# LED_Chaser.net
KiCad netlist of a schematic drawn in Altium Designer
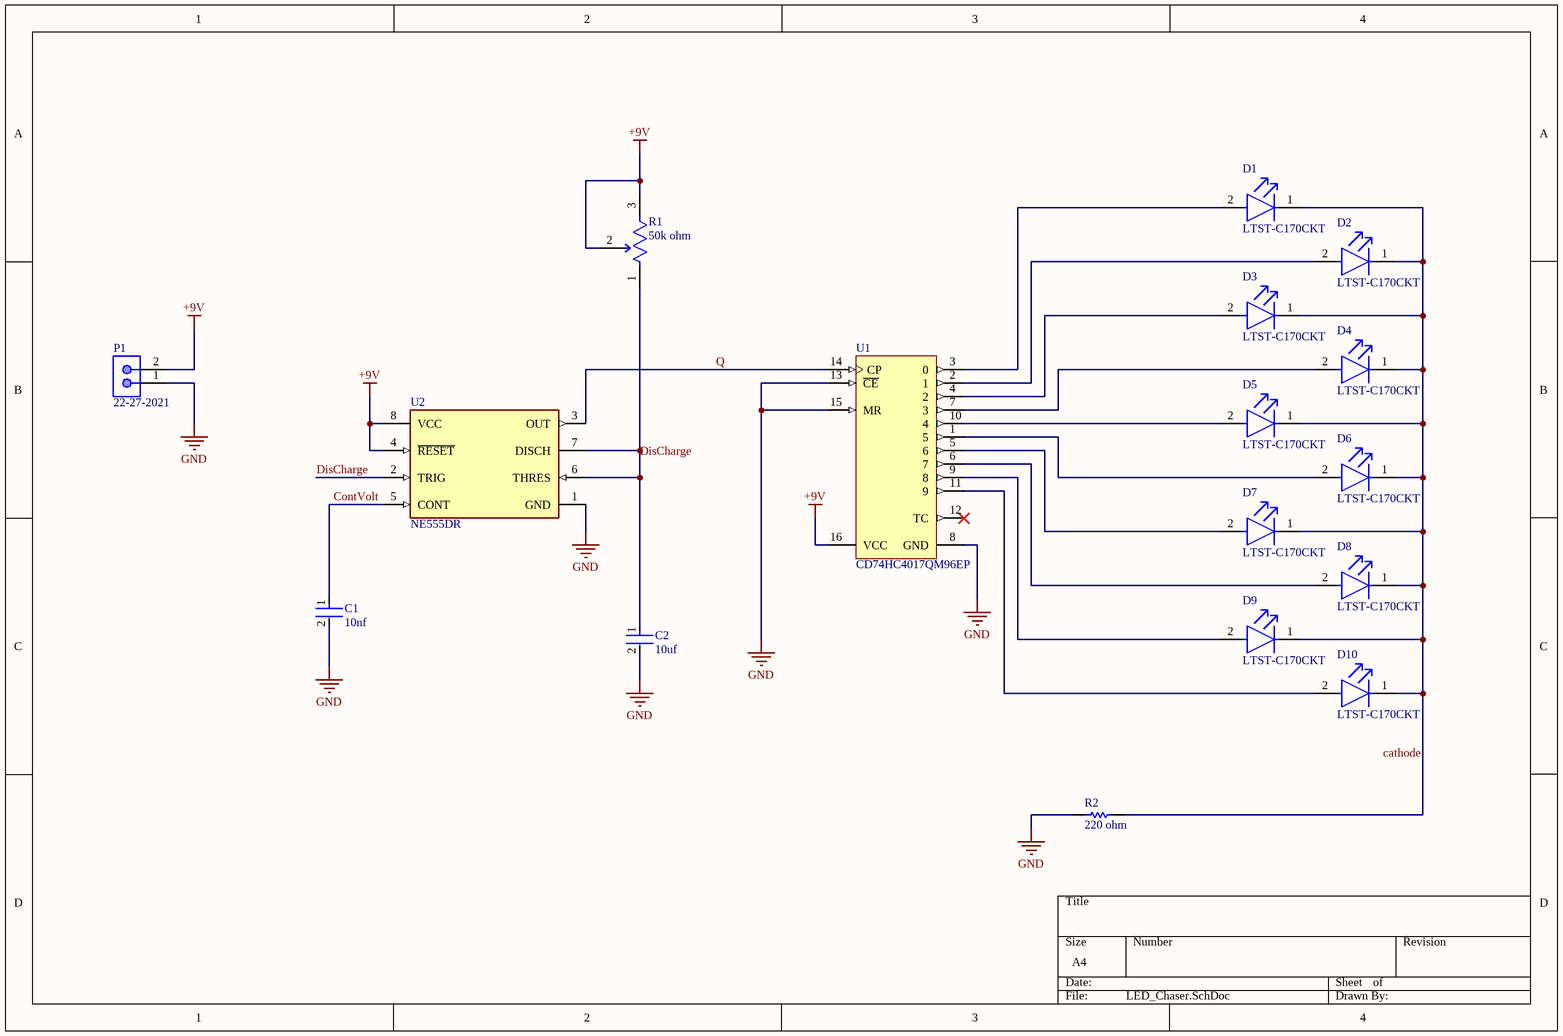
[diagram p0: LED_Chaser.SchDoc]

(export (version "E")
  (design (tool "Eeschema 10.0.6"))
  (components
    (comp (ref "C1")
      (value "10nf")
      (footprint "FP-CC0805-0_85-MFG")
      (description "CAP CER 0.1UF 50V X7R 0805")
      (fields (field (name "TOLERANCE") "0.1") (field (name "MANUFACTURER PART NUMBER") "CC0805KRX7R9BB104"))
      (libsource (lib "Altium Content Vault") (part "11868f565c42a9108669ba33697ecf6"))
    )
    (comp (ref "C2")
      (value "10uf")
      (footprint "FP-CC0805-0_85-MFG")
      (description "CAP CER 0.1UF 50V X7R 0805")
      (fields (field (name "TOLERANCE") "0.1") (field (name "MANUFACTURER PART NUMBER") "CC0805KRX7R9BB104"))
      (libsource (lib "Altium Content Vault") (part "11868f565c42a9108669ba33697ecf6"))
    )
    (comp (ref "D1")
      (value "LTST-C170CKT")
      (footprint "FP-LTST-C170CKT-MFG")
      (description "LED RED CLEAR SMD")
      (fields (field (name "VOLTAGE") "5V"))
      (libsource (lib "Altium Content Vault") (part "8706943c75ba83719d021d2fdc84c58"))
    )
    (comp (ref "D2")
      (value "LTST-C170CKT")
      (footprint "FP-LTST-C170CKT-MFG")
      (description "LED RED CLEAR SMD")
      (fields (field (name "VOLTAGE") "5V"))
      (libsource (lib "Altium Content Vault") (part "8706943c75ba83719d021d2fdc84c58"))
    )
    (comp (ref "D3")
      (value "LTST-C170CKT")
      (footprint "FP-LTST-C170CKT-MFG")
      (description "LED RED CLEAR SMD")
      (fields (field (name "VOLTAGE") "5V"))
      (libsource (lib "Altium Content Vault") (part "8706943c75ba83719d021d2fdc84c58"))
    )
    (comp (ref "D4")
      (value "LTST-C170CKT")
      (footprint "FP-LTST-C170CKT-MFG")
      (description "LED RED CLEAR SMD")
      (fields (field (name "VOLTAGE") "5V"))
      (libsource (lib "Altium Content Vault") (part "8706943c75ba83719d021d2fdc84c58"))
    )
    (comp (ref "D5")
      (value "LTST-C170CKT")
      (footprint "FP-LTST-C170CKT-MFG")
      (description "LED RED CLEAR SMD")
      (fields (field (name "VOLTAGE") "5V"))
      (libsource (lib "Altium Content Vault") (part "8706943c75ba83719d021d2fdc84c58"))
    )
    (comp (ref "D6")
      (value "LTST-C170CKT")
      (footprint "FP-LTST-C170CKT-MFG")
      (description "LED RED CLEAR SMD")
      (fields (field (name "VOLTAGE") "5V"))
      (libsource (lib "Altium Content Vault") (part "8706943c75ba83719d021d2fdc84c58"))
    )
    (comp (ref "D7")
      (value "LTST-C170CKT")
      (footprint "FP-LTST-C170CKT-MFG")
      (description "LED RED CLEAR SMD")
      (fields (field (name "VOLTAGE") "5V"))
      (libsource (lib "Altium Content Vault") (part "8706943c75ba83719d021d2fdc84c58"))
    )
    (comp (ref "D8")
      (value "LTST-C170CKT")
      (footprint "FP-LTST-C170CKT-MFG")
      (description "LED RED CLEAR SMD")
      (fields (field (name "VOLTAGE") "5V"))
      (libsource (lib "Altium Content Vault") (part "8706943c75ba83719d021d2fdc84c58"))
    )
    (comp (ref "D9")
      (value "LTST-C170CKT")
      (footprint "FP-LTST-C170CKT-MFG")
      (description "LED RED CLEAR SMD")
      (fields (field (name "VOLTAGE") "5V"))
      (libsource (lib "Altium Content Vault") (part "8706943c75ba83719d021d2fdc84c58"))
    )
    (comp (ref "D10")
      (value "LTST-C170CKT")
      (footprint "FP-LTST-C170CKT-MFG")
      (description "LED RED CLEAR SMD")
      (fields (field (name "VOLTAGE") "5V"))
      (libsource (lib "Altium Content Vault") (part "8706943c75ba83719d021d2fdc84c58"))
    )
    (comp (ref "P1")
      (value "22-27-2021")
      (footprint "MOLX-22-27-2021_V")
      (fields (field (name "MANUFACTURER") "Molex") (field (name "PARTNUMBER") "0022272021"))
      (libsource (lib "Altium Content Vault") (part "CN-1P-M-R2"))
    )
    (comp (ref "R1")
      (value "50k ohm")
      (footprint "FP-3361P-MFG")
      (description "TRIMMER 50K OHM 0.5W GW TOP ADJ")
      (fields (field (name "TOLERANCE") "10%"))
      (libsource (lib "Altium Content Vault") (part "13357d81287629c2fd191d242cfa50c"))
    )
    (comp (ref "R2")
      (value "220 ohm")
      (footprint "RESC2013X60X35ML10T20")
      (description "Chip Resistor, 1 KOhm, +/- 1%, 125 mW, -55 to 155 degC, 0805 (2012 Metric), RoHS, Tape and Reel")
      (fields (field (name "TOLERANCE") "1%") (field (name "MANUFACTURER") "Yageo"))
      (libsource (lib "Altium Content Vault") (part "RES-2"))
    )
    (comp (ref "U1")
      (value "CD74HC4017QM96EP")
      (footprint "D0016A_L")
      (description "Enhanced Product Decade Counter/Divider With 10 Decoded Outputs, D0016A, LARGE T&R")
      (fields
        (field (name "MANUFACTURER") "Texas Instruments")
        (field (name "GENERIC PART NUMBER") "CD74HC4017-EP")
      )
      (libsource (lib "Altium Content Vault") (part "TI-CD74HC4017-16"))
    )
    (comp (ref "U2")
      (value "NE555DR")
      (footprint "FP-D0008A-IPC_A")
      (description "IC OSC SGL TIMER 100KHZ 8-SOIC")
      (libsource (lib "Altium Content Vault") (part "a29bba90211dec1890110b94dad7d53"))
    )
  )
  (nets
    (net (code "1") (name "+9V") (class "Default")
      (node (ref "P1") (pin "2") (pinfunction "2_2") (pintype "passive"))
      (node (ref "R1") (pin "2") (pinfunction "WIPER_2") (pintype "passive"))
      (node (ref "R1") (pin "3") (pinfunction "CW_3") (pintype "passive"))
      (node (ref "U1") (pin "16") (pinfunction "VCC_16") (pintype "power_in"))
      (node (ref "U2") (pin "4") (pinfunction "~{RESET}_4") (pintype "input"))
      (node (ref "U2") (pin "8") (pinfunction "VCC_8") (pintype "power_in"))
    )
    (net (code "2") (name "/ContVolt") (class "Default")
      (node (ref "C1") (pin "1") (pinfunction "1_1") (pintype "passive"))
      (node (ref "U2") (pin "5") (pinfunction "CONT_5") (pintype "input"))
    )
    (net (code "3") (name "/DisCharge") (class "Default")
      (node (ref "C2") (pin "1") (pinfunction "1_1") (pintype "passive"))
      (node (ref "R1") (pin "1") (pinfunction "CCW_1") (pintype "passive"))
      (node (ref "U2") (pin "2") (pinfunction "TRIG_2") (pintype "input"))
      (node (ref "U2") (pin "6") (pinfunction "THRES_6") (pintype "input"))
      (node (ref "U2") (pin "7") (pinfunction "DISCH_7") (pintype "open_collector"))
    )
    (net (code "4") (name "/Q") (class "Default")
      (node (ref "U1") (pin "14") (pinfunction "CP_14") (pintype "input"))
      (node (ref "U2") (pin "3") (pinfunction "OUT_3") (pintype "output"))
    )
    (net (code "5") (name "/cathode") (class "Default")
      (node (ref "D1") (pin "1") (pinfunction "C_1") (pintype "passive"))
      (node (ref "D10") (pin "1") (pinfunction "C_1") (pintype "passive"))
      (node (ref "D2") (pin "1") (pinfunction "C_1") (pintype "passive"))
      (node (ref "D3") (pin "1") (pinfunction "C_1") (pintype "passive"))
      (node (ref "D4") (pin "1") (pinfunction "C_1") (pintype "passive"))
      (node (ref "D5") (pin "1") (pinfunction "C_1") (pintype "passive"))
      (node (ref "D6") (pin "1") (pinfunction "C_1") (pintype "passive"))
      (node (ref "D7") (pin "1") (pinfunction "C_1") (pintype "passive"))
      (node (ref "D8") (pin "1") (pinfunction "C_1") (pintype "passive"))
      (node (ref "D9") (pin "1") (pinfunction "C_1") (pintype "passive"))
      (node (ref "R2") (pin "2") (pinfunction "2_2") (pintype "passive"))
    )
    (net (code "6") (name "GND") (class "Default")
      (node (ref "C1") (pin "2") (pinfunction "2_2") (pintype "passive"))
      (node (ref "C2") (pin "2") (pinfunction "2_2") (pintype "passive"))
      (node (ref "P1") (pin "1") (pinfunction "1_1") (pintype "passive"))
      (node (ref "R2") (pin "1") (pinfunction "1_1") (pintype "passive"))
      (node (ref "U1") (pin "13") (pinfunction "~{CE}_13") (pintype "input"))
      (node (ref "U1") (pin "15") (pinfunction "MR_15") (pintype "input"))
      (node (ref "U1") (pin "8") (pinfunction "GND_8") (pintype "power_in"))
      (node (ref "U2") (pin "1") (pinfunction "GND_1") (pintype "power_in"))
    )
    (net (code "7") (name "Net-(D1-A)") (class "Default")
      (node (ref "D1") (pin "2") (pinfunction "A_2") (pintype "passive"))
      (node (ref "U1") (pin "3") (pinfunction "0_3") (pintype "output"))
    )
    (net (code "8") (name "Net-(D2-A)") (class "Default")
      (node (ref "D2") (pin "2") (pinfunction "A_2") (pintype "passive"))
      (node (ref "U1") (pin "2") (pinfunction "1_2") (pintype "output"))
    )
    (net (code "9") (name "Net-(D3-A)") (class "Default")
      (node (ref "D3") (pin "2") (pinfunction "A_2") (pintype "passive"))
      (node (ref "U1") (pin "4") (pinfunction "2_4") (pintype "output"))
    )
    (net (code "10") (name "Net-(D4-A)") (class "Default")
      (node (ref "D4") (pin "2") (pinfunction "A_2") (pintype "passive"))
      (node (ref "U1") (pin "7") (pinfunction "3_7") (pintype "output"))
    )
    (net (code "11") (name "Net-(D5-A)") (class "Default")
      (node (ref "D5") (pin "2") (pinfunction "A_2") (pintype "passive"))
      (node (ref "U1") (pin "10") (pinfunction "4_10") (pintype "output"))
    )
    (net (code "12") (name "Net-(D6-A)") (class "Default")
      (node (ref "D6") (pin "2") (pinfunction "A_2") (pintype "passive"))
      (node (ref "U1") (pin "1") (pinfunction "5_1") (pintype "output"))
    )
    (net (code "13") (name "Net-(D7-A)") (class "Default")
      (node (ref "D7") (pin "2") (pinfunction "A_2") (pintype "passive"))
      (node (ref "U1") (pin "5") (pinfunction "6_5") (pintype "output"))
    )
    (net (code "14") (name "Net-(D8-A)") (class "Default")
      (node (ref "D8") (pin "2") (pinfunction "A_2") (pintype "passive"))
      (node (ref "U1") (pin "6") (pinfunction "7_6") (pintype "output"))
    )
    (net (code "15") (name "Net-(D9-A)") (class "Default")
      (node (ref "D9") (pin "2") (pinfunction "A_2") (pintype "passive"))
      (node (ref "U1") (pin "9") (pinfunction "8_9") (pintype "output"))
    )
    (net (code "16") (name "Net-(D10-A)") (class "Default")
      (node (ref "D10") (pin "2") (pinfunction "A_2") (pintype "passive"))
      (node (ref "U1") (pin "11") (pinfunction "9_11") (pintype "output"))
    )
    (net (code "17") (name "unconnected-(U1-TC-Pad12)") (class "Default")
      (node (ref "U1") (pin "12") (pinfunction "TC_12") (pintype "output+no_connect"))
    )
  )
)
